# ESP32_VGA_Pocket.net
KiCad netlist of a schematic drawn in EAGLE
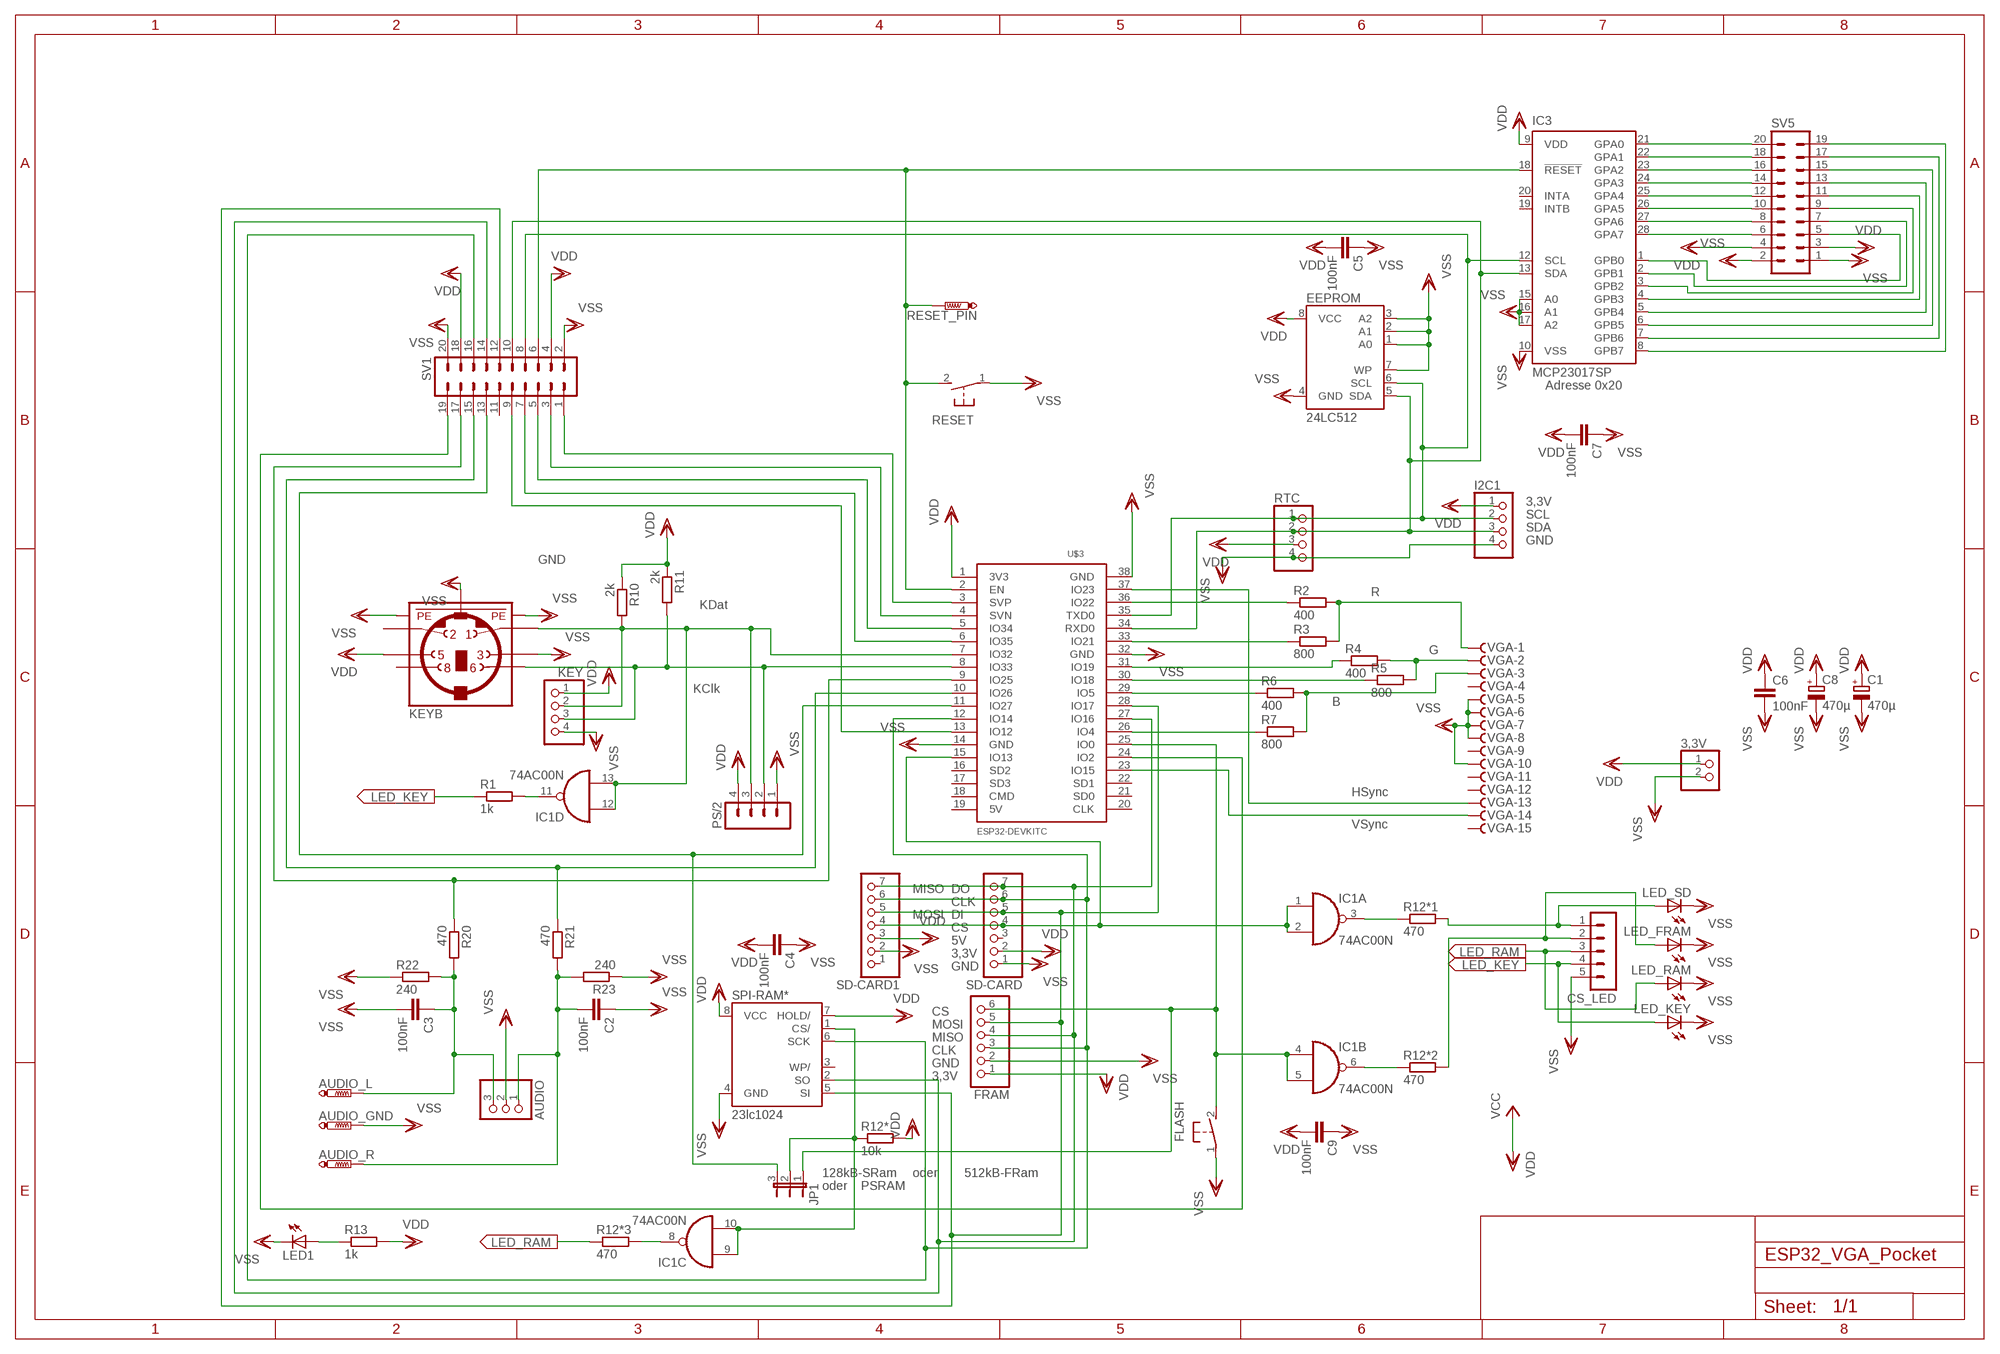
[diagram p0: schematic, sheet 1]

(export (version "E")
  (design (tool "Eeschema 10.0.6"))
  (components
    (comp (ref "3,3V")
      (value "PINHD-1X2")
      (footprint "eagle-import:1X02")
      (libsource (lib "eagle-import") (part "PINHD-1X2"))
    )
    (comp (ref "AUDIO")
      (value "PINHD-1X3")
      (footprint "eagle-import:1X03")
      (libsource (lib "eagle-import") (part "PINHD-1X3"))
    )
    (comp (ref "AUDIO_GND")
      (value "PTR1PAD1-13Y")
      (footprint "eagle-import:P1-13Y")
      (libsource (lib "eagle-import") (part "PTR1PAD1-13Y"))
    )
    (comp (ref "AUDIO_L")
      (value "PTR1PAD1-13Y")
      (footprint "eagle-import:P1-13Y")
      (libsource (lib "eagle-import") (part "PTR1PAD1-13Y"))
    )
    (comp (ref "AUDIO_R")
      (value "PTR1PAD1-13Y")
      (footprint "eagle-import:P1-13Y")
      (libsource (lib "eagle-import") (part "PTR1PAD1-13Y"))
    )
    (comp (ref "C1")
      (value "470µ")
      (footprint "eagle-import:E3,5-10")
      (libsource (lib "eagle-import") (part "CPOL-EUE3.5-10"))
    )
    (comp (ref "C2")
      (value "100nF")
      (footprint "eagle-import:C025-030X050")
      (libsource (lib "eagle-import") (part "C-EU025-030X050"))
    )
    (comp (ref "C3")
      (value "100nF")
      (footprint "eagle-import:C025-030X050")
      (libsource (lib "eagle-import") (part "C-EU025-030X050"))
    )
    (comp (ref "C4")
      (value "100nF")
      (footprint "eagle-import:C025-030X050")
      (libsource (lib "eagle-import") (part "C-EU025-030X050"))
    )
    (comp (ref "C5")
      (value "100nF")
      (footprint "eagle-import:C025-030X050")
      (libsource (lib "eagle-import") (part "C-EU025-030X050"))
    )
    (comp (ref "C6")
      (value "100nF")
      (footprint "eagle-import:C025-030X050")
      (libsource (lib "eagle-import") (part "C-EU025-030X050"))
    )
    (comp (ref "C7")
      (value "100nF")
      (footprint "eagle-import:C025-030X050")
      (libsource (lib "eagle-import") (part "C-EU025-030X050"))
    )
    (comp (ref "C8")
      (value "470µ")
      (footprint "eagle-import:E3,5-10")
      (libsource (lib "eagle-import") (part "CPOL-EUE3.5-10"))
    )
    (comp (ref "C9")
      (value "100nF")
      (footprint "eagle-import:C025-030X050")
      (libsource (lib "eagle-import") (part "C-EU025-030X050"))
    )
    (comp (ref "CS_LED")
      (value "MA05-1")
      (footprint "eagle-import:MA05-1")
      (libsource (lib "eagle-import") (part "MA05-1"))
    )
    (comp (ref "EEPROM")
      (value "24LC512")
      (footprint "eagle-import:DIL08")
      (fields (field (name "MPN") "AT24C1024BW-SH-B"))
      (libsource (lib "eagle-import") (part "AT24CP"))
    )
    (comp (ref "FLASH")
      (value "31-XX")
      (footprint "eagle-import:B3F-31XX")
      (fields
        (field (name "MPN") "B3F-3100")
        (field (name "MPN_1") "B3F-3100")
        (field (name "OC_FARNELL") "959704")
        (field (name "OC_NEWARK") "36M3582")
      )
      (libsource (lib "eagle-import") (part "31-XX"))
    )
    (comp (ref "FRAM")
      (value "PINHD-1X6")
      (footprint "eagle-import:1X06")
      (libsource (lib "eagle-import") (part "PINHD-1X6"))
    )
    (comp (ref "I2C1")
      (value "PINHD-1X4")
      (footprint "eagle-import:1X04")
      (libsource (lib "eagle-import") (part "PINHD-1X4"))
    )
    (comp (ref "IC1")
      (value "74AC00N")
      (footprint "eagle-import:DIL14")
      (libsource (lib "eagle-import") (part "7400NAC"))
    )
    (comp (ref "IC3")
      (value "MCP23017SP")
      (footprint "eagle-import:DIL28-3")
      (fields
        (field (name "MF") "MICROCHIP")
        (field (name "MPN") "MCP23017-E/SP")
        (field (name "MPN_1") "MCP23017-E/SO")
        (field (name "OC_FARNELL") "1332087")
        (field (name "OC_NEWARK") "31K2958")
      )
      (libsource (lib "eagle-import") (part "MCP23017SP"))
    )
    (comp (ref "JP1")
      (value "JP2E")
      (footprint "eagle-import:JP2")
      (libsource (lib "eagle-import") (part "JP2E"))
    )
    (comp (ref "KEY")
      (value "PINHD-1X4")
      (footprint "eagle-import:1X04")
      (libsource (lib "eagle-import") (part "PINHD-1X4"))
    )
    (comp (ref "KEYB")
      (value "MINI_DIN_6")
      (footprint "eagle-import:M_DIN6")
      (libsource (lib "eagle-import") (part "MINI_DIN_6"))
    )
    (comp (ref "LED1")
      (value "LED5MM")
      (footprint "eagle-import:LED5MM")
      (libsource (lib "eagle-import") (part "LED5MM"))
    )
    (comp (ref "LED_FRAM")
      (value "LED5MM")
      (footprint "eagle-import:LED5MM")
      (libsource (lib "eagle-import") (part "LED5MM"))
    )
    (comp (ref "LED_KEY")
      (value "LED5MM")
      (footprint "eagle-import:LED5MM")
      (libsource (lib "eagle-import") (part "LED5MM"))
    )
    (comp (ref "LED_RAM")
      (value "LED5MM")
      (footprint "eagle-import:LED5MM")
      (libsource (lib "eagle-import") (part "LED5MM"))
    )
    (comp (ref "LED_SD")
      (value "LED5MM")
      (footprint "eagle-import:LED5MM")
      (libsource (lib "eagle-import") (part "LED5MM"))
    )
    (comp (ref "PS/2")
      (value "MA04-1")
      (footprint "eagle-import:MA04-1")
      (libsource (lib "eagle-import") (part "MA04-1"))
    )
    (comp (ref "R1")
      (value "1k")
      (footprint "eagle-import:0204_7")
      (libsource (lib "eagle-import") (part "R-EU_0204/7"))
    )
    (comp (ref "R2")
      (value "400")
      (footprint "eagle-import:0204_7")
      (libsource (lib "eagle-import") (part "R-EU_0204/7"))
    )
    (comp (ref "R3")
      (value "800")
      (footprint "eagle-import:0204_7")
      (libsource (lib "eagle-import") (part "R-EU_0204/7"))
    )
    (comp (ref "R4")
      (value "400")
      (footprint "eagle-import:0204_7")
      (libsource (lib "eagle-import") (part "R-EU_0204/7"))
    )
    (comp (ref "R5")
      (value "800")
      (footprint "eagle-import:0204_7")
      (libsource (lib "eagle-import") (part "R-EU_0204/7"))
    )
    (comp (ref "R6")
      (value "400")
      (footprint "eagle-import:0204_7")
      (libsource (lib "eagle-import") (part "R-EU_0204/7"))
    )
    (comp (ref "R7")
      (value "800")
      (footprint "eagle-import:0204_7")
      (libsource (lib "eagle-import") (part "R-EU_0204/7"))
    )
    (comp (ref "R10")
      (value "2k")
      (footprint "eagle-import:0204_7")
      (libsource (lib "eagle-import") (part "R-EU_0204/7"))
    )
    (comp (ref "R11")
      (value "2k")
      (footprint "eagle-import:0204_7")
      (libsource (lib "eagle-import") (part "R-EU_0204/7"))
    )
    (comp (ref "R12*")
      (value "10k")
      (footprint "eagle-import:0204_7")
      (libsource (lib "eagle-import") (part "R-EU_0204/7"))
    )
    (comp (ref "R12*1")
      (value "470")
      (footprint "eagle-import:0204_7")
      (libsource (lib "eagle-import") (part "R-EU_0204/7"))
    )
    (comp (ref "R12*2")
      (value "470")
      (footprint "eagle-import:0204_7")
      (libsource (lib "eagle-import") (part "R-EU_0204/7"))
    )
    (comp (ref "R12*3")
      (value "470")
      (footprint "eagle-import:0204_7")
      (libsource (lib "eagle-import") (part "R-EU_0204/7"))
    )
    (comp (ref "R13")
      (value "1k")
      (footprint "eagle-import:0204_7")
      (libsource (lib "eagle-import") (part "R-EU_0204/7"))
    )
    (comp (ref "R20")
      (value "470")
      (footprint "eagle-import:0204_7")
      (libsource (lib "eagle-import") (part "R-EU_0204/7"))
    )
    (comp (ref "R21")
      (value "470")
      (footprint "eagle-import:0204_7")
      (libsource (lib "eagle-import") (part "R-EU_0204/7"))
    )
    (comp (ref "R22")
      (value "240")
      (footprint "eagle-import:0204_7")
      (libsource (lib "eagle-import") (part "R-EU_0204/7"))
    )
    (comp (ref "R23")
      (value "240")
      (footprint "eagle-import:0204_7")
      (libsource (lib "eagle-import") (part "R-EU_0204/7"))
    )
    (comp (ref "RESET")
      (value "31-XX")
      (footprint "eagle-import:B3F-31XX")
      (fields (field (name "MPN") "B3F-3100"))
      (libsource (lib "eagle-import") (part "31-XX"))
    )
    (comp (ref "RESET_PIN")
      (value "PTR1PAD1-17Y")
      (footprint "eagle-import:P1-17Y")
      (libsource (lib "eagle-import") (part "PTR1PAD1-17Y"))
    )
    (comp (ref "RTC")
      (value "PINHD-1X4")
      (footprint "eagle-import:1X04")
      (libsource (lib "eagle-import") (part "PINHD-1X4"))
    )
    (comp (ref "SD-CARD")
      (value "PINHD-1X7")
      (footprint "eagle-import:1X07")
      (libsource (lib "eagle-import") (part "PINHD-1X7"))
    )
    (comp (ref "SD-CARD1")
      (value "PINHD-1X7")
      (footprint "eagle-import:1X07")
      (libsource (lib "eagle-import") (part "PINHD-1X7"))
    )
    (comp (ref "SPI-RAM*")
      (value "23lc1024")
      (footprint "eagle-import:DIL08")
      (fields (field (name "MPN") "CAT25040LI-G"))
      (libsource (lib "eagle-import") (part "AT25P"))
    )
    (comp (ref "SV1")
      (value "MA10-2")
      (footprint "eagle-import:MA10-2")
      (libsource (lib "eagle-import") (part "MA10-2"))
    )
    (comp (ref "SV5")
      (value "MA10-2")
      (footprint "eagle-import:MA10-2")
      (libsource (lib "eagle-import") (part "MA10-2"))
    )
    (comp (ref "U$3")
      (value "ESP32DEVKITC")
      (footprint "eagle-import:ESP32-DEVKITC")
      (libsource (lib "eagle-import") (part "ESP32DEVKITC"))
    )
    (comp (ref "VGA")
      (value "F15HDHS")
      (footprint "eagle-import:HDF15H")
      (libsource (lib "eagle-import") (part "F15?SHDH"))
    )
  )
  (nets
    (net (code "1") (name "/LED_KEY") (class "Default")
      (node (ref "CS_LED") (pin "4") (pinfunction "4_4") (pintype "passive"))
      (node (ref "LED_KEY") (pin "A") (pinfunction "A_A") (pintype "passive"))
      (node (ref "R1") (pin "1") (pinfunction "1_1") (pintype "passive"))
    )
    (net (code "2") (name "/LED_RAM") (class "Default")
      (node (ref "CS_LED") (pin "3") (pinfunction "3_3") (pintype "passive"))
      (node (ref "LED_RAM") (pin "A") (pinfunction "A_A") (pintype "passive"))
      (node (ref "R12*3") (pin "1") (pinfunction "1_1") (pintype "passive"))
    )
    (net (code "3") (name "Net-(AUDIO-Pad1)") (class "Default")
      (node (ref "AUDIO") (pin "1") (pinfunction "1_1") (pintype "passive"))
      (node (ref "AUDIO_R") (pin "TP") (pinfunction "TP_TP") (pintype "input"))
      (node (ref "C2") (pin "2") (pinfunction "2_2") (pintype "passive"))
      (node (ref "R21") (pin "2") (pinfunction "2_2") (pintype "passive"))
      (node (ref "R23") (pin "2") (pinfunction "2_2") (pintype "passive"))
    )
    (net (code "4") (name "Net-(AUDIO-Pad3)") (class "Default")
      (node (ref "AUDIO") (pin "3") (pinfunction "3_3") (pintype "passive"))
      (node (ref "AUDIO_L") (pin "TP") (pinfunction "TP_TP") (pintype "input"))
      (node (ref "C3") (pin "1") (pinfunction "1_1") (pintype "passive"))
      (node (ref "R20") (pin "2") (pinfunction "2_2") (pintype "passive"))
      (node (ref "R22") (pin "2") (pinfunction "2_2") (pintype "passive"))
    )
    (net (code "5") (name "Net-(CS_LED-Pad1)") (class "Default")
      (node (ref "CS_LED") (pin "1") (pinfunction "1_1") (pintype "passive"))
      (node (ref "LED_SD") (pin "A") (pinfunction "A_A") (pintype "passive"))
      (node (ref "R12*1") (pin "2") (pinfunction "2_2") (pintype "passive"))
    )
    (net (code "6") (name "Net-(CS_LED-Pad2)") (class "Default")
      (node (ref "CS_LED") (pin "2") (pinfunction "2_2") (pintype "passive"))
      (node (ref "LED_FRAM") (pin "A") (pinfunction "A_A") (pintype "passive"))
      (node (ref "R12*2") (pin "2") (pinfunction "2_2") (pintype "passive"))
    )
    (net (code "7") (name "Net-(EEPROM-SCL)") (class "Default")
      (node (ref "EEPROM") (pin "6") (pinfunction "SCL_6") (pintype "bidirectional"))
      (node (ref "I2C1") (pin "2") (pinfunction "2_2") (pintype "passive"))
      (node (ref "IC3") (pin "12") (pinfunction "SCL_12") (pintype "input"))
      (node (ref "RTC") (pin "1") (pinfunction "1_1") (pintype "passive"))
      (node (ref "SV1") (pin "8") (pinfunction "8_8") (pintype "passive"))
      (node (ref "U$3") (pin "35") (pinfunction "TXD0_35") (pintype "bidirectional"))
    )
    (net (code "8") (name "Net-(EEPROM-SDA)") (class "Default")
      (node (ref "EEPROM") (pin "5") (pinfunction "SDA_5") (pintype "bidirectional"))
      (node (ref "I2C1") (pin "3") (pinfunction "3_3") (pintype "passive"))
      (node (ref "IC3") (pin "13") (pinfunction "SDA_13") (pintype "bidirectional"))
      (node (ref "RTC") (pin "2") (pinfunction "2_2") (pintype "passive"))
      (node (ref "SV1") (pin "10") (pinfunction "10_10") (pintype "passive"))
      (node (ref "U$3") (pin "34") (pinfunction "RXD0_34") (pintype "bidirectional"))
    )
    (net (code "9") (name "Net-(FLASH-S)") (class "Default")
      (node (ref "FLASH") (pin "2") (pinfunction "S_2") (pintype "passive"))
      (node (ref "FRAM") (pin "6") (pinfunction "6_6") (pintype "passive"))
      (node (ref "IC1") (pin "4") (pinfunction "I0_4") (pintype "input"))
      (node (ref "IC1") (pin "5") (pinfunction "I1_5") (pintype "input"))
      (node (ref "JP1") (pin "1") (pinfunction "1_1") (pintype "passive"))
      (node (ref "U$3") (pin "25") (pinfunction "IO0_25") (pintype "bidirectional"))
    )
    (net (code "10") (name "Net-(IC1A-I0)") (class "Default")
      (node (ref "IC1") (pin "1") (pinfunction "I0_1") (pintype "input"))
      (node (ref "IC1") (pin "2") (pinfunction "I1_2") (pintype "input"))
      (node (ref "SD-CARD") (pin "4") (pinfunction "4_4") (pintype "passive"))
      (node (ref "SD-CARD1") (pin "4") (pinfunction "4_4") (pintype "passive"))
      (node (ref "U$3") (pin "15") (pinfunction "IO13_15") (pintype "bidirectional"))
    )
    (net (code "11") (name "Net-(IC1A-O)") (class "Default")
      (node (ref "IC1") (pin "3") (pinfunction "O_3") (pintype "output"))
      (node (ref "R12*1") (pin "1") (pinfunction "1_1") (pintype "passive"))
    )
    (net (code "12") (name "Net-(IC1B-O)") (class "Default")
      (node (ref "IC1") (pin "6") (pinfunction "O_6") (pintype "output"))
      (node (ref "R12*2") (pin "1") (pinfunction "1_1") (pintype "passive"))
    )
    (net (code "13") (name "Net-(IC1C-I0)") (class "Default")
      (node (ref "IC1") (pin "10") (pinfunction "I1_10") (pintype "input"))
      (node (ref "IC1") (pin "9") (pinfunction "I0_9") (pintype "input"))
      (node (ref "JP1") (pin "2") (pinfunction "2_2") (pintype "passive"))
      (node (ref "R12*") (pin "1") (pinfunction "1_1") (pintype "passive"))
      (node (ref "SPI-RAM*") (pin "1") (pinfunction "CS/_1") (pintype "input"))
    )
    (net (code "14") (name "Net-(IC1C-O)") (class "Default")
      (node (ref "IC1") (pin "8") (pinfunction "O_8") (pintype "output"))
      (node (ref "R12*3") (pin "2") (pinfunction "2_2") (pintype "passive"))
    )
    (net (code "15") (name "Net-(IC1D-I0)") (class "Default")
      (node (ref "IC1") (pin "12") (pinfunction "I0_12") (pintype "input"))
      (node (ref "IC1") (pin "13") (pinfunction "I1_13") (pintype "input"))
      (node (ref "KEY") (pin "2") (pinfunction "2_2") (pintype "passive"))
      (node (ref "KEYB") (pin "1") (pinfunction "1_1") (pintype "passive"))
      (node (ref "PS/2") (pin "3") (pinfunction "3_3") (pintype "passive"))
      (node (ref "R10") (pin "2") (pinfunction "2_2") (pintype "passive"))
      (node (ref "U$3") (pin "7") (pinfunction "IO32_7") (pintype "bidirectional"))
    )
    (net (code "16") (name "Net-(IC1D-O)") (class "Default")
      (node (ref "IC1") (pin "11") (pinfunction "O_11") (pintype "output"))
      (node (ref "R1") (pin "2") (pinfunction "2_2") (pintype "passive"))
    )
    (net (code "17") (name "Net-(IC3-GPA0)") (class "Default")
      (node (ref "IC3") (pin "21") (pinfunction "GPA0_21") (pintype "bidirectional"))
      (node (ref "SV5") (pin "20") (pinfunction "20_20") (pintype "passive"))
    )
    (net (code "18") (name "Net-(IC3-GPA1)") (class "Default")
      (node (ref "IC3") (pin "22") (pinfunction "GPA1_22") (pintype "bidirectional"))
      (node (ref "SV5") (pin "18") (pinfunction "18_18") (pintype "passive"))
    )
    (net (code "19") (name "Net-(IC3-GPA2)") (class "Default")
      (node (ref "IC3") (pin "23") (pinfunction "GPA2_23") (pintype "bidirectional"))
      (node (ref "SV5") (pin "16") (pinfunction "16_16") (pintype "passive"))
    )
    (net (code "20") (name "Net-(IC3-GPA3)") (class "Default")
      (node (ref "IC3") (pin "24") (pinfunction "GPA3_24") (pintype "bidirectional"))
      (node (ref "SV5") (pin "14") (pinfunction "14_14") (pintype "passive"))
    )
    (net (code "21") (name "Net-(IC3-GPA4)") (class "Default")
      (node (ref "IC3") (pin "25") (pinfunction "GPA4_25") (pintype "bidirectional"))
      (node (ref "SV5") (pin "12") (pinfunction "12_12") (pintype "passive"))
    )
    (net (code "22") (name "Net-(IC3-GPA5)") (class "Default")
      (node (ref "IC3") (pin "26") (pinfunction "GPA5_26") (pintype "bidirectional"))
      (node (ref "SV5") (pin "10") (pinfunction "10_10") (pintype "passive"))
    )
    (net (code "23") (name "Net-(IC3-GPA6)") (class "Default")
      (node (ref "IC3") (pin "27") (pinfunction "GPA6_27") (pintype "bidirectional"))
      (node (ref "SV5") (pin "8") (pinfunction "8_8") (pintype "passive"))
    )
    (net (code "24") (name "Net-(IC3-GPA7)") (class "Default")
      (node (ref "IC3") (pin "28") (pinfunction "GPA7_28") (pintype "bidirectional"))
      (node (ref "SV5") (pin "6") (pinfunction "6_6") (pintype "passive"))
    )
    (net (code "25") (name "Net-(IC3-GPB0)") (class "Default")
      (node (ref "IC3") (pin "1") (pinfunction "GPB0_1") (pintype "bidirectional"))
      (node (ref "SV5") (pin "5") (pinfunction "5_5") (pintype "passive"))
    )
    (net (code "26") (name "Net-(IC3-GPB1)") (class "Default")
      (node (ref "IC3") (pin "2") (pinfunction "GPB1_2") (pintype "bidirectional"))
      (node (ref "SV5") (pin "7") (pinfunction "7_7") (pintype "passive"))
    )
    (net (code "27") (name "Net-(IC3-GPB2)") (class "Default")
      (node (ref "IC3") (pin "3") (pinfunction "GPB2_3") (pintype "bidirectional"))
      (node (ref "SV5") (pin "9") (pinfunction "9_9") (pintype "passive"))
    )
    (net (code "28") (name "Net-(IC3-GPB3)") (class "Default")
      (node (ref "IC3") (pin "4") (pinfunction "GPB3_4") (pintype "bidirectional"))
      (node (ref "SV5") (pin "11") (pinfunction "11_11") (pintype "passive"))
    )
    (net (code "29") (name "Net-(IC3-GPB4)") (class "Default")
      (node (ref "IC3") (pin "5") (pinfunction "GPB4_5") (pintype "bidirectional"))
      (node (ref "SV5") (pin "13") (pinfunction "13_13") (pintype "passive"))
    )
    (net (code "30") (name "Net-(IC3-GPB5)") (class "Default")
      (node (ref "IC3") (pin "6") (pinfunction "GPB5_6") (pintype "bidirectional"))
      (node (ref "SV5") (pin "15") (pinfunction "15_15") (pintype "passive"))
    )
    (net (code "31") (name "Net-(IC3-GPB6)") (class "Default")
      (node (ref "IC3") (pin "7") (pinfunction "GPB6_7") (pintype "bidirectional"))
      (node (ref "SV5") (pin "17") (pinfunction "17_17") (pintype "passive"))
    )
    (net (code "32") (name "Net-(IC3-GPB7)") (class "Default")
      (node (ref "IC3") (pin "8") (pinfunction "GPB7_8") (pintype "bidirectional"))
      (node (ref "SV5") (pin "19") (pinfunction "19_19") (pintype "passive"))
    )
    (net (code "33") (name "Net-(IC3-~{RESET})") (class "Default")
      (node (ref "IC3") (pin "18") (pinfunction "~{RESET}_18") (pintype "input"))
      (node (ref "RESET") (pin "2") (pinfunction "S_2") (pintype "passive"))
      (node (ref "RESET_PIN") (pin "TP") (pinfunction "TP_TP") (pintype "input"))
      (node (ref "SV1") (pin "6") (pinfunction "6_6") (pintype "passive"))
      (node (ref "U$3") (pin "2") (pinfunction "EN_2") (pintype "bidirectional"))
    )
    (net (code "34") (name "Net-(LED1-PadA)") (class "Default")
      (node (ref "LED1") (pin "A") (pinfunction "A_A") (pintype "passive"))
      (node (ref "R13") (pin "1") (pinfunction "1_1") (pintype "passive"))
    )
    (net (code "35") (name "Net-(SPI-RAM*-SCK)") (class "Default")
      (node (ref "FRAM") (pin "3") (pinfunction "3_3") (pintype "passive"))
      (node (ref "SD-CARD") (pin "6") (pinfunction "6_6") (pintype "passive"))
      (node (ref "SD-CARD1") (pin "6") (pinfunction "6_6") (pintype "passive"))
      (node (ref "SPI-RAM*") (pin "6") (pinfunction "SCK_6") (pintype "bidirectional"))
      (node (ref "SV1") (pin "16") (pinfunction "16_16") (pintype "passive"))
      (node (ref "U$3") (pin "12") (pinfunction "IO14_12") (pintype "bidirectional"))
    )
    (net (code "36") (name "Net-(SPI-RAM*-SI)") (class "Default")
      (node (ref "FRAM") (pin "5") (pinfunction "5_5") (pintype "passive"))
      (node (ref "SD-CARD") (pin "5") (pinfunction "5_5") (pintype "passive"))
      (node (ref "SD-CARD1") (pin "5") (pinfunction "5_5") (pintype "passive"))
      (node (ref "SPI-RAM*") (pin "5") (pinfunction "SI_5") (pintype "bidirectional"))
      (node (ref "SV1") (pin "12") (pinfunction "12_12") (pintype "passive"))
      (node (ref "U$3") (pin "28") (pinfunction "IO17_28") (pintype "bidirectional"))
    )
    (net (code "37") (name "Net-(SPI-RAM*-SO)") (class "Default")
      (node (ref "FRAM") (pin "4") (pinfunction "4_4") (pintype "passive"))
      (node (ref "SD-CARD") (pin "7") (pinfunction "7_7") (pintype "passive"))
      (node (ref "SD-CARD1") (pin "7") (pinfunction "7_7") (pintype "passive"))
      (node (ref "SPI-RAM*") (pin "2") (pinfunction "SO_2") (pintype "input"))
      (node (ref "SV1") (pin "14") (pinfunction "14_14") (pintype "passive"))
      (node (ref "U$3") (pin "27") (pinfunction "IO16_27") (pintype "bidirectional"))
    )
    (net (code "38") (name "Net-(U$3-IO2)") (class "Default")
      (node (ref "SV1") (pin "19") (pinfunction "19_19") (pintype "passive"))
      (node (ref "U$3") (pin "24") (pinfunction "IO2_24") (pintype "bidirectional"))
    )
    (net (code "39") (name "Net-(U$3-IO4)") (class "Default")
      (node (ref "R7") (pin "1") (pinfunction "1_1") (pintype "passive"))
      (node (ref "U$3") (pin "26") (pinfunction "IO4_26") (pintype "bidirectional"))
    )
    (net (code "40") (name "Net-(U$3-IO5)") (class "Default")
      (node (ref "R6") (pin "1") (pinfunction "1_1") (pintype "passive"))
      (node (ref "U$3") (pin "29") (pinfunction "IO5_29") (pintype "bidirectional"))
    )
    (net (code "41") (name "Net-(U$3-IO12)") (class "Default")
      (node (ref "SV1") (pin "9") (pinfunction "9_9") (pintype "passive"))
      (node (ref "U$3") (pin "13") (pinfunction "IO12_13") (pintype "bidirectional"))
    )
    (net (code "42") (name "Net-(U$3-IO15)") (class "Default")
      (node (ref "U$3") (pin "23") (pinfunction "IO15_23") (pintype "bidirectional"))
      (node (ref "VGA") (pin "14") (pinfunction "F_14") (pintype "passive"))
    )
    (net (code "43") (name "Net-(U$3-IO18)") (class "Default")
      (node (ref "R5") (pin "1") (pinfunction "1_1") (pintype "passive"))
      (node (ref "U$3") (pin "30") (pinfunction "IO18_30") (pintype "bidirectional"))
    )
    (net (code "44") (name "Net-(U$3-IO19)") (class "Default")
      (node (ref "R4") (pin "1") (pinfunction "1_1") (pintype "passive"))
      (node (ref "U$3") (pin "31") (pinfunction "IO19_31") (pintype "bidirectional"))
    )
    (net (code "45") (name "Net-(U$3-IO21)") (class "Default")
      (node (ref "R3") (pin "1") (pinfunction "1_1") (pintype "passive"))
      (node (ref "U$3") (pin "33") (pinfunction "IO21_33") (pintype "bidirectional"))
    )
    (net (code "46") (name "Net-(U$3-IO22)") (class "Default")
      (node (ref "R2") (pin "1") (pinfunction "1_1") (pintype "passive"))
      (node (ref "U$3") (pin "36") (pinfunction "IO22_36") (pintype "bidirectional"))
    )
    (net (code "47") (name "Net-(U$3-IO23)") (class "Default")
      (node (ref "U$3") (pin "37") (pinfunction "IO23_37") (pintype "bidirectional"))
      (node (ref "VGA") (pin "13") (pinfunction "F_13") (pintype "passive"))
    )
    (net (code "48") (name "Net-(U$3-IO25)") (class "Default")
      (node (ref "R20") (pin "1") (pinfunction "1_1") (pintype "passive"))
      (node (ref "SV1") (pin "17") (pinfunction "17_17") (pintype "passive"))
      (node (ref "U$3") (pin "9") (pinfunction "IO25_9") (pintype "bidirectional"))
    )
    (net (code "49") (name "Net-(U$3-IO26)") (class "Default")
      (node (ref "R21") (pin "1") (pinfunction "1_1") (pintype "passive"))
      (node (ref "SV1") (pin "15") (pinfunction "15_15") (pintype "passive"))
      (node (ref "U$3") (pin "10") (pinfunction "IO26_10") (pintype "bidirectional"))
    )
    (net (code "50") (name "Net-(U$3-IO27)") (class "Default")
      (node (ref "JP1") (pin "3") (pinfunction "3_3") (pintype "passive"))
      (node (ref "SV1") (pin "13") (pinfunction "13_13") (pintype "passive"))
      (node (ref "U$3") (pin "11") (pinfunction "IO27_11") (pintype "bidirectional"))
    )
    (net (code "51") (name "Net-(U$3-IO33)") (class "Default")
      (node (ref "KEY") (pin "3") (pinfunction "3_3") (pintype "passive"))
      (node (ref "KEYB") (pin "6") (pinfunction "6_6") (pintype "passive"))
      (node (ref "PS/2") (pin "2") (pinfunction "2_2") (pintype "passive"))
      (node (ref "R11") (pin "2") (pinfunction "2_2") (pintype "passive"))
      (node (ref "U$3") (pin "8") (pinfunction "IO33_8") (pintype "bidirectional"))
    )
    (net (code "52") (name "Net-(U$3-IO34)") (class "Default")
      (node (ref "SV1") (pin "5") (pinfunction "5_5") (pintype "passive"))
      (node (ref "U$3") (pin "5") (pinfunction "IO34_5") (pintype "bidirectional"))
    )
    (net (code "53") (name "Net-(U$3-IO35)") (class "Default")
      (node (ref "SV1") (pin "7") (pinfunction "7_7") (pintype "passive"))
      (node (ref "U$3") (pin "6") (pinfunction "IO35_6") (pintype "bidirectional"))
    )
    (net (code "54") (name "Net-(U$3-SVN)") (class "Default")
      (node (ref "SV1") (pin "3") (pinfunction "3_3") (pintype "passive"))
      (node (ref "U$3") (pin "4") (pinfunction "SVN_4") (pintype "bidirectional"))
    )
    (net (code "55") (name "Net-(U$3-SVP)") (class "Default")
      (node (ref "SV1") (pin "1") (pinfunction "1_1") (pintype "passive"))
      (node (ref "U$3") (pin "3") (pinfunction "SVP_3") (pintype "bidirectional"))
    )
    (net (code "56") (name "Net-(VGAA-F)") (class "Default")
      (node (ref "R2") (pin "2") (pinfunction "2_2") (pintype "passive"))
      (node (ref "R3") (pin "2") (pinfunction "2_2") (pintype "passive"))
      (node (ref "VGA") (pin "1") (pinfunction "F_1") (pintype "passive"))
    )
    (net (code "57") (name "Net-(VGAH-F)") (class "Default")
      (node (ref "R4") (pin "2") (pinfunction "2_2") (pintype "passive"))
      (node (ref "R5") (pin "2") (pinfunction "2_2") (pintype "passive"))
      (node (ref "VGA") (pin "2") (pinfunction "F_2") (pintype "passive"))
    )
    (net (code "58") (name "Net-(VGAI-F)") (class "Default")
      (node (ref "R6") (pin "2") (pinfunction "2_2") (pintype "passive"))
      (node (ref "R7") (pin "2") (pinfunction "2_2") (pintype "passive"))
      (node (ref "VGA") (pin "3") (pinfunction "F_3") (pintype "passive"))
    )
    (net (code "59") (name "VCC") (class "Default")
      (node (ref "3,3V") (pin "1") (pinfunction "1_1") (pintype "passive"))
      (node (ref "C1") (pin "+") (pinfunction "+_+") (pintype "passive"))
      (node (ref "C4") (pin "2") (pinfunction "2_2") (pintype "passive"))
      (node (ref "C5") (pin "2") (pinfunction "2_2") (pintype "passive"))
      (node (ref "C6") (pin "1") (pinfunction "1_1") (pintype "passive"))
      (node (ref "C7") (pin "2") (pinfunction "2_2") (pintype "passive"))
      (node (ref "C8") (pin "+") (pinfunction "+_+") (pintype "passive"))
      (node (ref "C9") (pin "2") (pinfunction "2_2") (pintype "passive"))
      (node (ref "EEPROM") (pin "8") (pinfunction "VCC_8") (pintype "power_in"))
      (node (ref "FRAM") (pin "1") (pinfunction "1_1") (pintype "passive"))
      (node (ref "I2C1") (pin "1") (pinfunction "1_1") (pintype "passive"))
      (node (ref "IC3") (pin "9") (pinfunction "VDD_9") (pintype "power_in"))
      (node (ref "KEY") (pin "1") (pinfunction "1_1") (pintype "passive"))
      (node (ref "KEYB") (pin "5") (pinfunction "5_5") (pintype "passive"))
      (node (ref "PS/2") (pin "4") (pinfunction "4_4") (pintype "passive"))
      (node (ref "R10") (pin "1") (pinfunction "1_1") (pintype "passive"))
      (node (ref "R11") (pin "1") (pinfunction "1_1") (pintype "passive"))
      (node (ref "R12*") (pin "2") (pinfunction "2_2") (pintype "passive"))
      (node (ref "R13") (pin "2") (pinfunction "2_2") (pintype "passive"))
      (node (ref "RTC") (pin "3") (pinfunction "3_3") (pintype "passive"))
      (node (ref "SD-CARD") (pin "2") (pinfunction "2_2") (pintype "passive"))
      (node (ref "SD-CARD1") (pin "3") (pinfunction "3_3") (pintype "passive"))
      (node (ref "SPI-RAM*") (pin "7") (pinfunction "HOLD/_7") (pintype "input"))
      (node (ref "SPI-RAM*") (pin "8") (pinfunction "VCC_8") (pintype "power_in"))
      (node (ref "SV1") (pin "18") (pinfunction "18_18") (pintype "passive"))
      (node (ref "SV1") (pin "4") (pinfunction "4_4") (pintype "passive"))
      (node (ref "SV5") (pin "3") (pinfunction "3_3") (pintype "passive"))
      (node (ref "SV5") (pin "4") (pinfunction "4_4") (pintype "passive"))
      (node (ref "U$3") (pin "1") (pinfunction "3V3_1") (pintype "bidirectional"))
    )
    (net (code "60") (name "VSS") (class "Default")
      (node (ref "3,3V") (pin "2") (pinfunction "2_2") (pintype "passive"))
      (node (ref "AUDIO") (pin "2") (pinfunction "2_2") (pintype "passive"))
      (node (ref "AUDIO_GND") (pin "TP") (pinfunction "TP_TP") (pintype "input"))
      (node (ref "C1") (pin "-") (pinfunction "-_-") (pintype "passive"))
      (node (ref "C2") (pin "1") (pinfunction "1_1") (pintype "passive"))
      (node (ref "C3") (pin "2") (pinfunction "2_2") (pintype "passive"))
      (node (ref "C4") (pin "1") (pinfunction "1_1") (pintype "passive"))
      (node (ref "C5") (pin "1") (pinfunction "1_1") (pintype "passive"))
      (node (ref "C6") (pin "2") (pinfunction "2_2") (pintype "passive"))
      (node (ref "C7") (pin "1") (pinfunction "1_1") (pintype "passive"))
      (node (ref "C8") (pin "-") (pinfunction "-_-") (pintype "passive"))
      (node (ref "C9") (pin "1") (pinfunction "1_1") (pintype "passive"))
      (node (ref "CS_LED") (pin "5") (pinfunction "5_5") (pintype "passive"))
      (node (ref "EEPROM") (pin "1") (pinfunction "A0_1") (pintype "input"))
      (node (ref "EEPROM") (pin "2") (pinfunction "A1_2") (pintype "input"))
      (node (ref "EEPROM") (pin "3") (pinfunction "A2_3") (pintype "input"))
      (node (ref "EEPROM") (pin "4") (pinfunction "GND_4") (pintype "power_in"))
      (node (ref "EEPROM") (pin "7") (pinfunction "WP_7") (pintype "input"))
      (node (ref "FLASH") (pin "1") (pinfunction "P_1") (pintype "passive"))
      (node (ref "FRAM") (pin "2") (pinfunction "2_2") (pintype "passive"))
      (node (ref "I2C1") (pin "4") (pinfunction "4_4") (pintype "passive"))
      (node (ref "IC3") (pin "10") (pinfunction "VSS_10") (pintype "power_in"))
      (node (ref "IC3") (pin "15") (pinfunction "A0_15") (pintype "input"))
      (node (ref "IC3") (pin "16") (pinfunction "A1_16") (pintype "input"))
      (node (ref "IC3") (pin "17") (pinfunction "A2_17") (pintype "input"))
      (node (ref "KEY") (pin "4") (pinfunction "4_4") (pintype "passive"))
      (node (ref "KEYB") (pin "3") (pinfunction "3_3") (pintype "passive"))
      (node (ref "KEYB") (pin "SH1") (pinfunction "PE1_SH1") (pintype "power_in"))
      (node (ref "KEYB") (pin "SH2") (pinfunction "PE2_SH2") (pintype "power_in"))
      (node (ref "KEYB") (pin "SH3") (pinfunction "PE3_SH3") (pintype "power_in"))
      (node (ref "LED1") (pin "K") (pinfunction "C_K") (pintype "passive"))
      (node (ref "LED_FRAM") (pin "K") (pinfunction "C_K") (pintype "passive"))
      (node (ref "LED_KEY") (pin "K") (pinfunction "C_K") (pintype "passive"))
      (node (ref "LED_RAM") (pin "K") (pinfunction "C_K") (pintype "passive"))
      (node (ref "LED_SD") (pin "K") (pinfunction "C_K") (pintype "passive"))
      (node (ref "PS/2") (pin "1") (pinfunction "1_1") (pintype "passive"))
      (node (ref "R22") (pin "1") (pinfunction "1_1") (pintype "passive"))
      (node (ref "R23") (pin "1") (pinfunction "1_1") (pintype "passive"))
      (node (ref "RESET") (pin "1") (pinfunction "P_1") (pintype "passive"))
      (node (ref "RTC") (pin "4") (pinfunction "4_4") (pintype "passive"))
      (node (ref "SD-CARD") (pin "1") (pinfunction "1_1") (pintype "passive"))
      (node (ref "SD-CARD1") (pin "2") (pinfunction "2_2") (pintype "passive"))
      (node (ref "SPI-RAM*") (pin "4") (pinfunction "GND_4") (pintype "power_in"))
      (node (ref "SV1") (pin "2") (pinfunction "2_2") (pintype "passive"))
      (node (ref "SV1") (pin "20") (pinfunction "20_20") (pintype "passive"))
      (node (ref "SV5") (pin "1") (pinfunction "1_1") (pintype "passive"))
      (node (ref "SV5") (pin "2") (pinfunction "2_2") (pintype "passive"))
      (node (ref "U$3") (pin "14") (pinfunction "GND_14") (pintype "bidirectional"))
      (node (ref "U$3") (pin "32") (pinfunction "GND_32") (pintype "bidirectional"))
      (node (ref "U$3") (pin "38") (pinfunction "GND_38") (pintype "bidirectional"))
      (node (ref "VGA") (pin "10") (pinfunction "F_10") (pintype "passive"))
      (node (ref "VGA") (pin "5") (pinfunction "F_5") (pintype "passive"))
      (node (ref "VGA") (pin "6") (pinfunction "F_6") (pintype "passive"))
      (node (ref "VGA") (pin "7") (pinfunction "F_7") (pintype "passive"))
      (node (ref "VGA") (pin "8") (pinfunction "F_8") (pintype "passive"))
    )
    (net (code "61") (name "unconnected-(IC3-INTA-Pad20)") (class "Default")
      (node (ref "IC3") (pin "20") (pinfunction "INTA_20") (pintype "output"))
    )
    (net (code "62") (name "unconnected-(IC3-INTB-Pad19)") (class "Default")
      (node (ref "IC3") (pin "19") (pinfunction "INTB_19") (pintype "output"))
    )
    (net (code "63") (name "unconnected-(KEYB-Pad2)") (class "Default")
      (node (ref "KEYB") (pin "2") (pinfunction "2_2") (pintype "passive"))
    )
    (net (code "64") (name "unconnected-(KEYB-Pad8)") (class "Default")
      (node (ref "KEYB") (pin "8") (pinfunction "8_8") (pintype "passive"))
    )
    (net (code "65") (name "unconnected-(SD-CARD-Pad3)") (class "Default")
      (node (ref "SD-CARD") (pin "3") (pinfunction "3_3") (pintype "passive"))
    )
    (net (code "66") (name "unconnected-(SD-CARD1-Pad1)") (class "Default")
      (node (ref "SD-CARD1") (pin "1") (pinfunction "1_1") (pintype "passive"))
    )
    (net (code "67") (name "unconnected-(SPI-RAM*-WP{slash}-Pad3)") (class "Default")
      (node (ref "SPI-RAM*") (pin "3") (pinfunction "WP/_3") (pintype "input"))
    )
    (net (code "68") (name "unconnected-(SV1-Pad11)") (class "Default")
      (node (ref "SV1") (pin "11") (pinfunction "11_11") (pintype "passive"))
    )
    (net (code "69") (name "unconnected-(U$3-5V-Pad19)") (class "Default")
      (node (ref "U$3") (pin "19") (pinfunction "5V_19") (pintype "bidirectional"))
    )
    (net (code "70") (name "unconnected-(U$3-CLK-Pad20)") (class "Default")
      (node (ref "U$3") (pin "20") (pinfunction "CLK_20") (pintype "bidirectional"))
    )
    (net (code "71") (name "unconnected-(U$3-CMD-Pad18)") (class "Default")
      (node (ref "U$3") (pin "18") (pinfunction "CMD_18") (pintype "bidirectional"))
    )
    (net (code "72") (name "unconnected-(U$3-SD0-Pad21)") (class "Default")
      (node (ref "U$3") (pin "21") (pinfunction "SD0_21") (pintype "bidirectional"))
    )
    (net (code "73") (name "unconnected-(U$3-SD1-Pad22)") (class "Default")
      (node (ref "U$3") (pin "22") (pinfunction "SD1_22") (pintype "bidirectional"))
    )
    (net (code "74") (name "unconnected-(U$3-SD2-Pad16)") (class "Default")
      (node (ref "U$3") (pin "16") (pinfunction "SD2_16") (pintype "bidirectional"))
    )
    (net (code "75") (name "unconnected-(U$3-SD3-Pad17)") (class "Default")
      (node (ref "U$3") (pin "17") (pinfunction "SD3_17") (pintype "bidirectional"))
    )
    (net (code "76") (name "unconnected-(VGAC-F-Pad11)") (class "Default")
      (node (ref "VGA") (pin "11") (pinfunction "F_11") (pintype "passive"))
    )
    (net (code "77") (name "unconnected-(VGAD-F-Pad12)") (class "Default")
      (node (ref "VGA") (pin "12") (pinfunction "F_12") (pintype "passive"))
    )
    (net (code "78") (name "unconnected-(VGAG-F-Pad15)") (class "Default")
      (node (ref "VGA") (pin "15") (pinfunction "F_15") (pintype "passive"))
    )
    (net (code "79") (name "unconnected-(VGAJ-F-Pad4)") (class "Default")
      (node (ref "VGA") (pin "4") (pinfunction "F_4") (pintype "passive"))
    )
    (net (code "80") (name "unconnected-(VGAO-F-Pad9)") (class "Default")
      (node (ref "VGA") (pin "9") (pinfunction "F_9") (pintype "passive"))
    )
  )
)
